# cpu_adapter.net
KiCad netlist of a schematic drawn in EAGLE
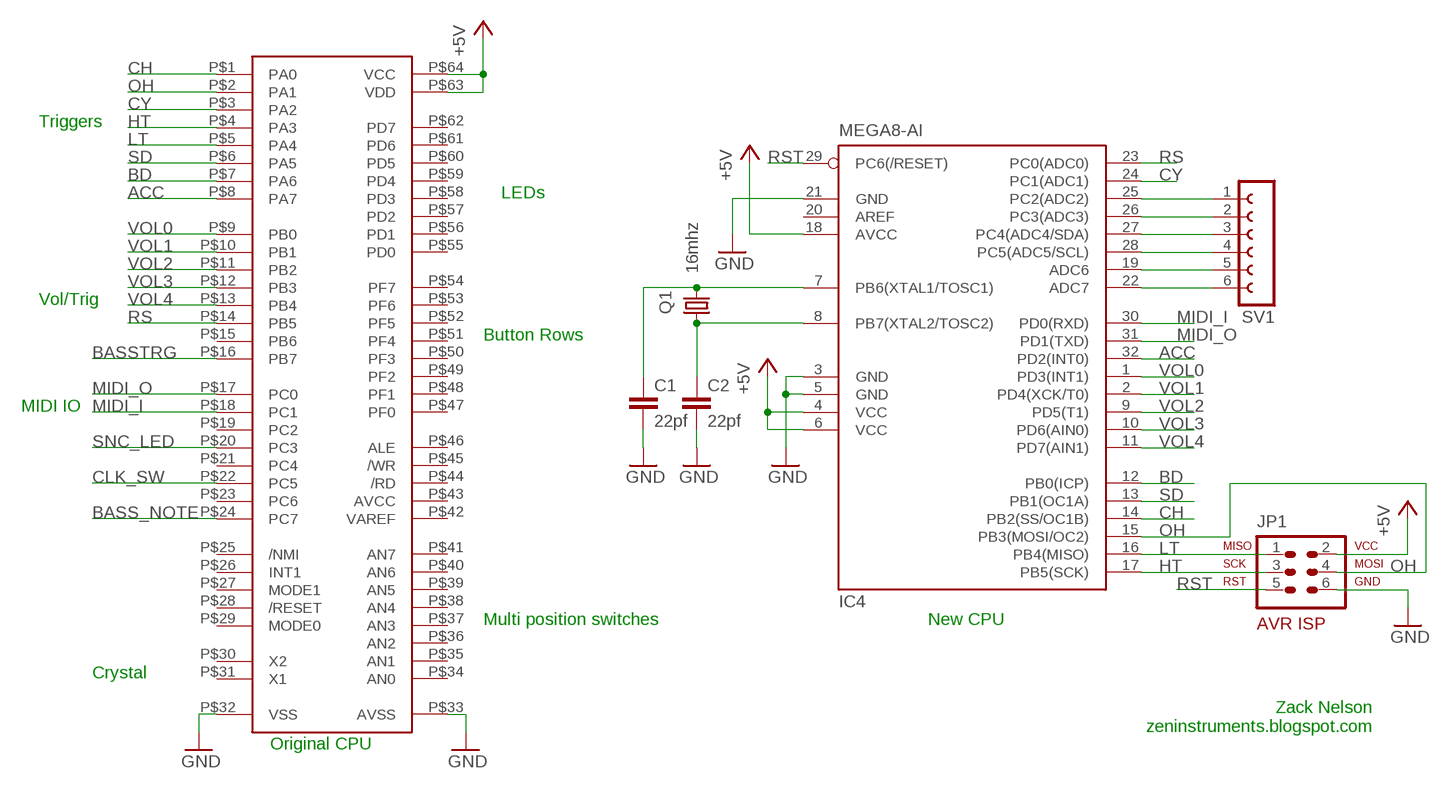
[diagram p0: schematic, sheet 1]

(export (version "E")
  (design (tool "Eeschema 10.0.6"))
  (components
    (comp (ref "C1")
      (value "22pf")
      (footprint "eagle-import:C025-024X044")
      (libsource (lib "eagle-import") (part "C-EU025-024X044"))
    )
    (comp (ref "C2")
      (value "22pf")
      (footprint "eagle-import:C025-024X044")
      (libsource (lib "eagle-import") (part "C-EU025-024X044"))
    )
    (comp (ref "IC1")
      (value "D7811G")
      (footprint "eagle-import:64STAG")
      (libsource (lib "eagle-import") (part "D7811G"))
    )
    (comp (ref "IC4")
      (value "MEGA8-AI")
      (footprint "eagle-import:TQFP32-08")
      (fields (field (name "MPN") "ATMEGA8-16AU"))
      (libsource (lib "eagle-import") (part "MEGA8-AI"))
    )
    (comp (ref "JP1")
      (value "AVR-ISP-6")
      (footprint "eagle-import:AVR-ISP-6")
      (libsource (lib "eagle-import") (part "AVR-ISP-6VERT"))
    )
    (comp (ref "Q1")
      (value "16mhz")
      (footprint "eagle-import:HC18U-V")
      (libsource (lib "eagle-import") (part "CRYSTALHC18U-V"))
    )
    (comp (ref "SV1")
      (value "FE06-1")
      (footprint "eagle-import:FE06")
      (libsource (lib "eagle-import") (part "FE06-1"))
    )
  )
  (nets
    (net (code "1") (name "+5V") (class "Default")
      (node (ref "IC1") (pin "P$63") (pinfunction "VDD_P$63") (pintype "bidirectional"))
      (node (ref "IC1") (pin "P$64") (pinfunction "VCC_P$64") (pintype "bidirectional"))
      (node (ref "IC4") (pin "18") (pinfunction "AVCC_18") (pintype "power_in"))
      (node (ref "IC4") (pin "4") (pinfunction "VCC_4") (pintype "power_in"))
      (node (ref "IC4") (pin "6") (pinfunction "VCC_6") (pintype "power_in"))
      (node (ref "JP1") (pin "2") (pinfunction "2_2") (pintype "passive"))
    )
    (net (code "2") (name "/ACC") (class "Default")
      (node (ref "IC1") (pin "P$8") (pinfunction "PA7_P$8") (pintype "bidirectional"))
      (node (ref "IC4") (pin "32") (pinfunction "PD2(INT0)_32") (pintype "bidirectional"))
    )
    (net (code "3") (name "/BASSTRG") (class "Default")
      (node (ref "IC1") (pin "P$16") (pinfunction "PB7_P$16") (pintype "bidirectional"))
    )
    (net (code "4") (name "/BASS_NOTE") (class "Default")
      (node (ref "IC1") (pin "P$24") (pinfunction "PC7_P$24") (pintype "bidirectional"))
    )
    (net (code "5") (name "/BD") (class "Default")
      (node (ref "IC1") (pin "P$7") (pinfunction "PA6_P$7") (pintype "bidirectional"))
      (node (ref "IC4") (pin "12") (pinfunction "PB0(ICP)_12") (pintype "bidirectional"))
    )
    (net (code "6") (name "/CH") (class "Default")
      (node (ref "IC1") (pin "P$1") (pinfunction "PA0_P$1") (pintype "bidirectional"))
      (node (ref "IC4") (pin "14") (pinfunction "PB2(SS/OC1B)_14") (pintype "bidirectional"))
    )
    (net (code "7") (name "/CLK_SW") (class "Default")
      (node (ref "IC1") (pin "P$22") (pinfunction "PC5_P$22") (pintype "bidirectional"))
    )
    (net (code "8") (name "/CY") (class "Default")
      (node (ref "IC1") (pin "P$3") (pinfunction "PA2_P$3") (pintype "bidirectional"))
      (node (ref "IC4") (pin "24") (pinfunction "PC1(ADC1)_24") (pintype "bidirectional"))
    )
    (net (code "9") (name "/HT") (class "Default")
      (node (ref "IC1") (pin "P$4") (pinfunction "PA3_P$4") (pintype "bidirectional"))
      (node (ref "IC4") (pin "17") (pinfunction "PB5(SCK)_17") (pintype "bidirectional"))
      (node (ref "JP1") (pin "3") (pinfunction "3_3") (pintype "passive"))
    )
    (net (code "10") (name "/LT") (class "Default")
      (node (ref "IC1") (pin "P$5") (pinfunction "PA4_P$5") (pintype "bidirectional"))
      (node (ref "IC4") (pin "16") (pinfunction "PB4(MISO)_16") (pintype "bidirectional"))
      (node (ref "JP1") (pin "1") (pinfunction "1_1") (pintype "passive"))
    )
    (net (code "11") (name "/MIDI_I") (class "Default")
      (node (ref "IC1") (pin "P$18") (pinfunction "PC1_P$18") (pintype "bidirectional"))
      (node (ref "IC4") (pin "30") (pinfunction "PD0(RXD)_30") (pintype "bidirectional"))
    )
    (net (code "12") (name "/MIDI_O") (class "Default")
      (node (ref "IC1") (pin "P$17") (pinfunction "PC0_P$17") (pintype "bidirectional"))
      (node (ref "IC4") (pin "31") (pinfunction "PD1(TXD)_31") (pintype "bidirectional"))
    )
    (net (code "13") (name "/OH") (class "Default")
      (node (ref "IC1") (pin "P$2") (pinfunction "PA1_P$2") (pintype "bidirectional"))
      (node (ref "IC4") (pin "15") (pinfunction "PB3(MOSI/OC2)_15") (pintype "bidirectional"))
      (node (ref "JP1") (pin "4") (pinfunction "4_4") (pintype "passive"))
    )
    (net (code "14") (name "/RS") (class "Default")
      (node (ref "IC1") (pin "P$14") (pinfunction "PB5_P$14") (pintype "bidirectional"))
      (node (ref "IC4") (pin "23") (pinfunction "PC0(ADC0)_23") (pintype "bidirectional"))
    )
    (net (code "15") (name "/RST") (class "Default")
      (node (ref "IC4") (pin "29") (pinfunction "PC6(/RESET)_29") (pintype "bidirectional"))
      (node (ref "JP1") (pin "5") (pinfunction "5_5") (pintype "passive"))
    )
    (net (code "16") (name "/SD") (class "Default")
      (node (ref "IC1") (pin "P$6") (pinfunction "PA5_P$6") (pintype "bidirectional"))
      (node (ref "IC4") (pin "13") (pinfunction "PB1(OC1A)_13") (pintype "bidirectional"))
    )
    (net (code "17") (name "/SNC_LED") (class "Default")
      (node (ref "IC1") (pin "P$20") (pinfunction "PC3_P$20") (pintype "bidirectional"))
    )
    (net (code "18") (name "/VOL0") (class "Default")
      (node (ref "IC1") (pin "P$9") (pinfunction "PB0_P$9") (pintype "bidirectional"))
      (node (ref "IC4") (pin "1") (pinfunction "PD3(INT1)_1") (pintype "bidirectional"))
    )
    (net (code "19") (name "/VOL1") (class "Default")
      (node (ref "IC1") (pin "P$10") (pinfunction "PB1_P$10") (pintype "bidirectional"))
      (node (ref "IC4") (pin "2") (pinfunction "PD4(XCK/T0)_2") (pintype "bidirectional"))
    )
    (net (code "20") (name "/VOL2") (class "Default")
      (node (ref "IC1") (pin "P$11") (pinfunction "PB2_P$11") (pintype "bidirectional"))
      (node (ref "IC4") (pin "9") (pinfunction "PD5(T1)_9") (pintype "bidirectional"))
    )
    (net (code "21") (name "/VOL3") (class "Default")
      (node (ref "IC1") (pin "P$12") (pinfunction "PB3_P$12") (pintype "bidirectional"))
      (node (ref "IC4") (pin "10") (pinfunction "PD6(AIN0)_10") (pintype "bidirectional"))
    )
    (net (code "22") (name "/VOL4") (class "Default")
      (node (ref "IC1") (pin "P$13") (pinfunction "PB4_P$13") (pintype "bidirectional"))
      (node (ref "IC4") (pin "11") (pinfunction "PD7(AIN1)_11") (pintype "bidirectional"))
    )
    (net (code "23") (name "GND") (class "Default")
      (node (ref "C1") (pin "2") (pinfunction "2_2") (pintype "passive"))
      (node (ref "C2") (pin "2") (pinfunction "2_2") (pintype "passive"))
      (node (ref "IC1") (pin "P$32") (pinfunction "VSS_P$32") (pintype "bidirectional"))
      (node (ref "IC1") (pin "P$33") (pinfunction "AVSS_P$33") (pintype "bidirectional"))
      (node (ref "IC4") (pin "21") (pinfunction "GND_21") (pintype "power_in"))
      (node (ref "IC4") (pin "3") (pinfunction "GND_3") (pintype "power_in"))
      (node (ref "IC4") (pin "5") (pinfunction "GND_5") (pintype "power_in"))
      (node (ref "JP1") (pin "6") (pinfunction "6_6") (pintype "passive"))
    )
    (net (code "24") (name "Net-(IC4-ADC6)") (class "Default")
      (node (ref "IC4") (pin "19") (pinfunction "ADC6_19") (pintype "bidirectional"))
      (node (ref "SV1") (pin "5") (pinfunction "5_5") (pintype "passive"))
    )
    (net (code "25") (name "Net-(IC4-ADC7)") (class "Default")
      (node (ref "IC4") (pin "22") (pinfunction "ADC7_22") (pintype "bidirectional"))
      (node (ref "SV1") (pin "6") (pinfunction "6_6") (pintype "passive"))
    )
    (net (code "26") (name "Net-(IC4-PB6(XTAL1{slash}TOSC1))") (class "Default")
      (node (ref "C1") (pin "1") (pinfunction "1_1") (pintype "passive"))
      (node (ref "IC4") (pin "7") (pinfunction "PB6(XTAL1/TOSC1)_7") (pintype "bidirectional"))
      (node (ref "Q1") (pin "2") (pinfunction "2_2") (pintype "passive"))
    )
    (net (code "27") (name "Net-(IC4-PB7(XTAL2{slash}TOSC2))") (class "Default")
      (node (ref "C2") (pin "1") (pinfunction "1_1") (pintype "passive"))
      (node (ref "IC4") (pin "8") (pinfunction "PB7(XTAL2/TOSC2)_8") (pintype "bidirectional"))
      (node (ref "Q1") (pin "1") (pinfunction "1_1") (pintype "passive"))
    )
    (net (code "28") (name "Net-(IC4-PC2(ADC2))") (class "Default")
      (node (ref "IC4") (pin "25") (pinfunction "PC2(ADC2)_25") (pintype "bidirectional"))
      (node (ref "SV1") (pin "1") (pinfunction "1_1") (pintype "passive"))
    )
    (net (code "29") (name "Net-(IC4-PC3(ADC3))") (class "Default")
      (node (ref "IC4") (pin "26") (pinfunction "PC3(ADC3)_26") (pintype "bidirectional"))
      (node (ref "SV1") (pin "2") (pinfunction "2_2") (pintype "passive"))
    )
    (net (code "30") (name "Net-(IC4-PC4(ADC4{slash}SDA))") (class "Default")
      (node (ref "IC4") (pin "27") (pinfunction "PC4(ADC4/SDA)_27") (pintype "bidirectional"))
      (node (ref "SV1") (pin "3") (pinfunction "3_3") (pintype "passive"))
    )
    (net (code "31") (name "Net-(IC4-PC5(ADC5{slash}SCL))") (class "Default")
      (node (ref "IC4") (pin "28") (pinfunction "PC5(ADC5/SCL)_28") (pintype "bidirectional"))
      (node (ref "SV1") (pin "4") (pinfunction "4_4") (pintype "passive"))
    )
    (net (code "32") (name "unconnected-(IC1-ALE-PadP$46)") (class "Default")
      (node (ref "IC1") (pin "P$46") (pinfunction "ALE_P$46") (pintype "bidirectional"))
    )
    (net (code "33") (name "unconnected-(IC1-AN0-PadP$34)") (class "Default")
      (node (ref "IC1") (pin "P$34") (pinfunction "AN0_P$34") (pintype "bidirectional"))
    )
    (net (code "34") (name "unconnected-(IC1-AN1-PadP$35)") (class "Default")
      (node (ref "IC1") (pin "P$35") (pinfunction "AN1_P$35") (pintype "bidirectional"))
    )
    (net (code "35") (name "unconnected-(IC1-AN2-PadP$36)") (class "Default")
      (node (ref "IC1") (pin "P$36") (pinfunction "AN2_P$36") (pintype "bidirectional"))
    )
    (net (code "36") (name "unconnected-(IC1-AN3-PadP$37)") (class "Default")
      (node (ref "IC1") (pin "P$37") (pinfunction "AN3_P$37") (pintype "bidirectional"))
    )
    (net (code "37") (name "unconnected-(IC1-AN4-PadP$38)") (class "Default")
      (node (ref "IC1") (pin "P$38") (pinfunction "AN4_P$38") (pintype "bidirectional"))
    )
    (net (code "38") (name "unconnected-(IC1-AN5-PadP$39)") (class "Default")
      (node (ref "IC1") (pin "P$39") (pinfunction "AN5_P$39") (pintype "bidirectional"))
    )
    (net (code "39") (name "unconnected-(IC1-AN6-PadP$40)") (class "Default")
      (node (ref "IC1") (pin "P$40") (pinfunction "AN6_P$40") (pintype "bidirectional"))
    )
    (net (code "40") (name "unconnected-(IC1-AN7-PadP$41)") (class "Default")
      (node (ref "IC1") (pin "P$41") (pinfunction "AN7_P$41") (pintype "bidirectional"))
    )
    (net (code "41") (name "unconnected-(IC1-AVCC-PadP$43)") (class "Default")
      (node (ref "IC1") (pin "P$43") (pinfunction "AVCC_P$43") (pintype "bidirectional"))
    )
    (net (code "42") (name "unconnected-(IC1-INT1-PadP$26)") (class "Default")
      (node (ref "IC1") (pin "P$26") (pinfunction "INT1_P$26") (pintype "bidirectional"))
    )
    (net (code "43") (name "unconnected-(IC1-MODE0-PadP$29)") (class "Default")
      (node (ref "IC1") (pin "P$29") (pinfunction "MODE0_P$29") (pintype "bidirectional"))
    )
    (net (code "44") (name "unconnected-(IC1-MODE1-PadP$27)") (class "Default")
      (node (ref "IC1") (pin "P$27") (pinfunction "MODE1_P$27") (pintype "bidirectional"))
    )
    (net (code "45") (name "unconnected-(IC1-PB6-PadP$15)") (class "Default")
      (node (ref "IC1") (pin "P$15") (pinfunction "PB6_P$15") (pintype "bidirectional"))
    )
    (net (code "46") (name "unconnected-(IC1-PC2-PadP$19)") (class "Default")
      (node (ref "IC1") (pin "P$19") (pinfunction "PC2_P$19") (pintype "bidirectional"))
    )
    (net (code "47") (name "unconnected-(IC1-PC4-PadP$21)") (class "Default")
      (node (ref "IC1") (pin "P$21") (pinfunction "PC4_P$21") (pintype "bidirectional"))
    )
    (net (code "48") (name "unconnected-(IC1-PC6-PadP$23)") (class "Default")
      (node (ref "IC1") (pin "P$23") (pinfunction "PC6_P$23") (pintype "bidirectional"))
    )
    (net (code "49") (name "unconnected-(IC1-PD0-PadP$55)") (class "Default")
      (node (ref "IC1") (pin "P$55") (pinfunction "PD0_P$55") (pintype "bidirectional"))
    )
    (net (code "50") (name "unconnected-(IC1-PD1-PadP$56)") (class "Default")
      (node (ref "IC1") (pin "P$56") (pinfunction "PD1_P$56") (pintype "bidirectional"))
    )
    (net (code "51") (name "unconnected-(IC1-PD2-PadP$57)") (class "Default")
      (node (ref "IC1") (pin "P$57") (pinfunction "PD2_P$57") (pintype "bidirectional"))
    )
    (net (code "52") (name "unconnected-(IC1-PD3-PadP$58)") (class "Default")
      (node (ref "IC1") (pin "P$58") (pinfunction "PD3_P$58") (pintype "bidirectional"))
    )
    (net (code "53") (name "unconnected-(IC1-PD4-PadP$59)") (class "Default")
      (node (ref "IC1") (pin "P$59") (pinfunction "PD4_P$59") (pintype "bidirectional"))
    )
    (net (code "54") (name "unconnected-(IC1-PD5-PadP$60)") (class "Default")
      (node (ref "IC1") (pin "P$60") (pinfunction "PD5_P$60") (pintype "bidirectional"))
    )
    (net (code "55") (name "unconnected-(IC1-PD6-PadP$61)") (class "Default")
      (node (ref "IC1") (pin "P$61") (pinfunction "PD6_P$61") (pintype "bidirectional"))
    )
    (net (code "56") (name "unconnected-(IC1-PD7-PadP$62)") (class "Default")
      (node (ref "IC1") (pin "P$62") (pinfunction "PD7_P$62") (pintype "bidirectional"))
    )
    (net (code "57") (name "unconnected-(IC1-PF0-PadP$47)") (class "Default")
      (node (ref "IC1") (pin "P$47") (pinfunction "PF0_P$47") (pintype "bidirectional"))
    )
    (net (code "58") (name "unconnected-(IC1-PF1-PadP$48)") (class "Default")
      (node (ref "IC1") (pin "P$48") (pinfunction "PF1_P$48") (pintype "bidirectional"))
    )
    (net (code "59") (name "unconnected-(IC1-PF2-PadP$49)") (class "Default")
      (node (ref "IC1") (pin "P$49") (pinfunction "PF2_P$49") (pintype "bidirectional"))
    )
    (net (code "60") (name "unconnected-(IC1-PF3-PadP$50)") (class "Default")
      (node (ref "IC1") (pin "P$50") (pinfunction "PF3_P$50") (pintype "bidirectional"))
    )
    (net (code "61") (name "unconnected-(IC1-PF4-PadP$51)") (class "Default")
      (node (ref "IC1") (pin "P$51") (pinfunction "PF4_P$51") (pintype "bidirectional"))
    )
    (net (code "62") (name "unconnected-(IC1-PF5-PadP$52)") (class "Default")
      (node (ref "IC1") (pin "P$52") (pinfunction "PF5_P$52") (pintype "bidirectional"))
    )
    (net (code "63") (name "unconnected-(IC1-PF6-PadP$53)") (class "Default")
      (node (ref "IC1") (pin "P$53") (pinfunction "PF6_P$53") (pintype "bidirectional"))
    )
    (net (code "64") (name "unconnected-(IC1-PF7-PadP$54)") (class "Default")
      (node (ref "IC1") (pin "P$54") (pinfunction "PF7_P$54") (pintype "bidirectional"))
    )
    (net (code "65") (name "unconnected-(IC1-VAREF-PadP$42)") (class "Default")
      (node (ref "IC1") (pin "P$42") (pinfunction "VAREF_P$42") (pintype "bidirectional"))
    )
    (net (code "66") (name "unconnected-(IC1-X1-PadP$31)") (class "Default")
      (node (ref "IC1") (pin "P$31") (pinfunction "X1_P$31") (pintype "bidirectional"))
    )
    (net (code "67") (name "unconnected-(IC1-X2-PadP$30)") (class "Default")
      (node (ref "IC1") (pin "P$30") (pinfunction "X2_P$30") (pintype "bidirectional"))
    )
    (net (code "68") (name "unconnected-(IC1-{slash}NMI-PadP$25)") (class "Default")
      (node (ref "IC1") (pin "P$25") (pinfunction "/NMI_P$25") (pintype "bidirectional"))
    )
    (net (code "69") (name "unconnected-(IC1-{slash}RD-PadP$44)") (class "Default")
      (node (ref "IC1") (pin "P$44") (pinfunction "/RD_P$44") (pintype "bidirectional"))
    )
    (net (code "70") (name "unconnected-(IC1-{slash}RESET-PadP$28)") (class "Default")
      (node (ref "IC1") (pin "P$28") (pinfunction "/RESET_P$28") (pintype "bidirectional"))
    )
    (net (code "71") (name "unconnected-(IC1-{slash}WR-PadP$45)") (class "Default")
      (node (ref "IC1") (pin "P$45") (pinfunction "/WR_P$45") (pintype "bidirectional"))
    )
    (net (code "72") (name "unconnected-(IC4-AREF-Pad20)") (class "Default")
      (node (ref "IC4") (pin "20") (pinfunction "AREF_20") (pintype "passive"))
    )
  )
)
